# alarmlight_v1_0.net
KiCad netlist of a schematic drawn in Altium Designer
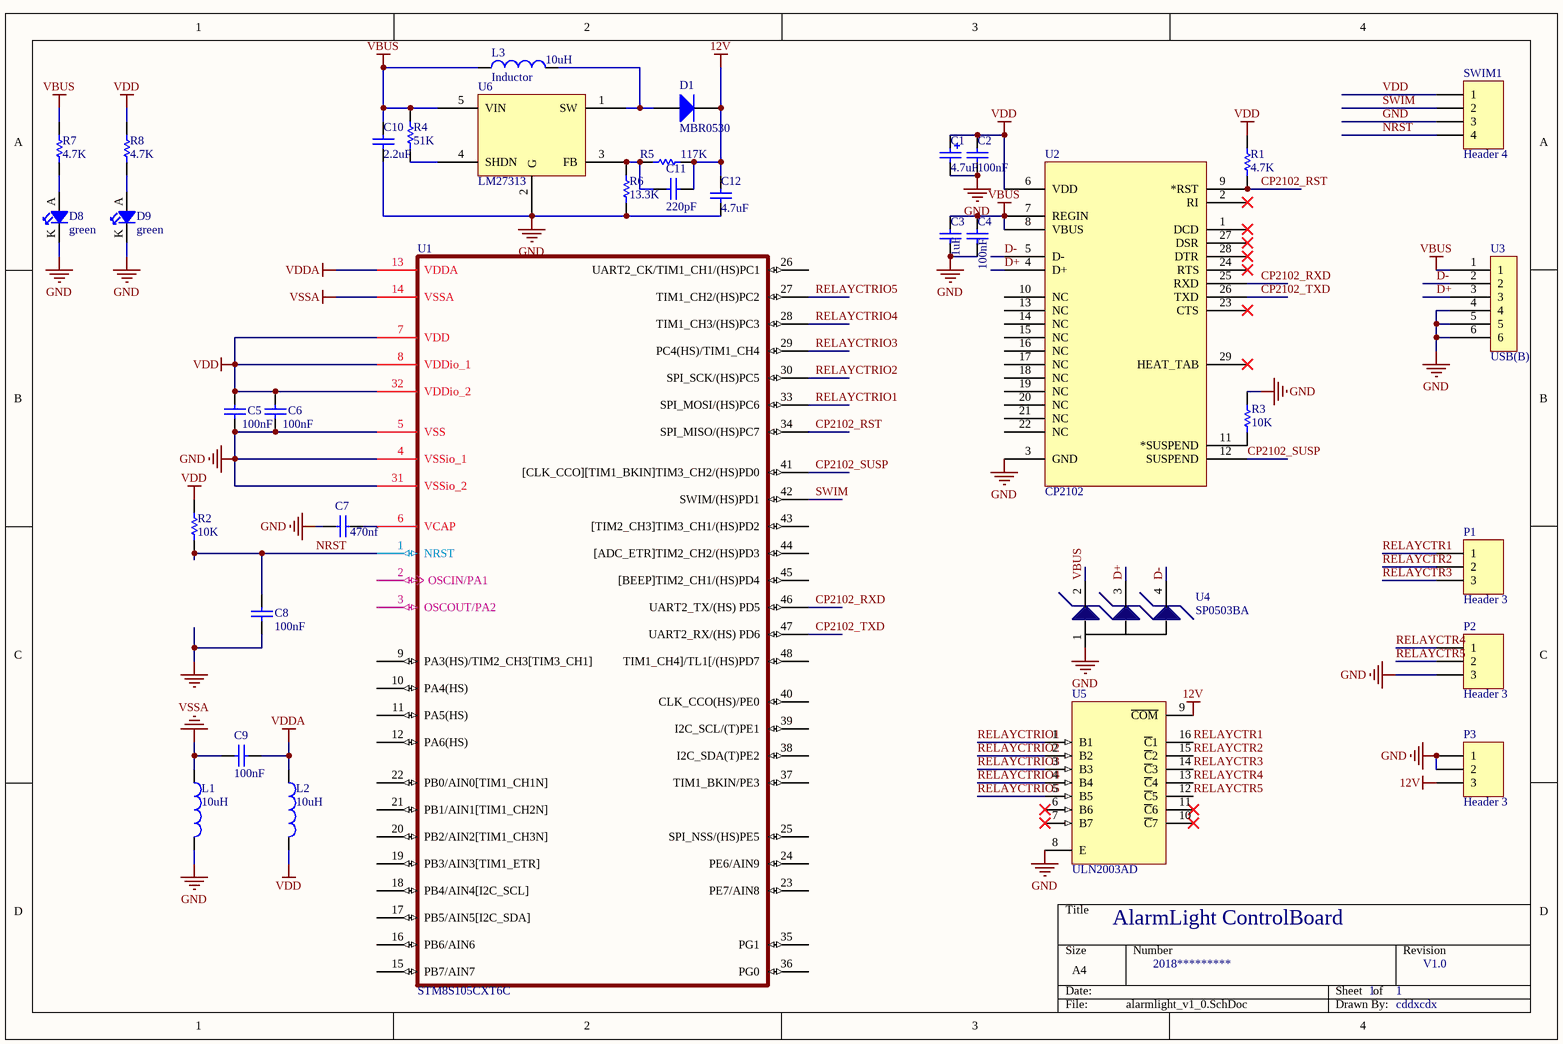
[diagram p0: alarmlight_v1_0.SchDoc]

(export (version "E")
  (design (tool "Eeschema 10.0.6"))
  (components
    (comp (ref "C1")
      (value "4.7uF")
      (footprint "TC3216")
      (description "Polarized Capacitor (Radial)")
      (fields (field (name "PUBLISHER") "Altium Limited"))
      (libsource (lib "MPU_V5") (part "Cap Pol1_4"))
    )
    (comp (ref "C2")
      (value "100nF")
      (footprint "0805C")
      (description "Capacitor")
      (fields (field (name "PUBLISHER") "Altium Limited"))
      (libsource (lib "Miscellaneous Devices") (part "CAP"))
    )
    (comp (ref "C3")
      (value "1uF")
      (footprint "0805C")
      (description "Capacitor")
      (fields (field (name "PUBLISHER") "Altium Limited"))
      (libsource (lib "Miscellaneous Devices") (part "CAP"))
    )
    (comp (ref "C4")
      (value "100nF")
      (footprint "0805C")
      (description "Capacitor")
      (fields (field (name "PUBLISHER") "Altium Limited"))
      (libsource (lib "Miscellaneous Devices") (part "CAP"))
    )
    (comp (ref "C5")
      (value "100nF")
      (footprint "0805C")
      (description "Capacitor")
      (fields (field (name "PUBLISHER") "Altium Limited"))
      (libsource (lib "Miscellaneous Devices") (part "CAP"))
    )
    (comp (ref "C6")
      (value "100nF")
      (footprint "0805C")
      (description "Capacitor")
      (fields (field (name "PUBLISHER") "Altium Limited"))
      (libsource (lib "Miscellaneous Devices") (part "CAP"))
    )
    (comp (ref "C7")
      (value "470nf")
      (footprint "0805C")
      (description "Capacitor")
      (fields (field (name "Comment") "Cap") (field (name "PUBLISHER") "Altium Limited"))
      (libsource (lib "Miscellaneous Devices") (part "Cap"))
    )
    (comp (ref "C8")
      (value "100nF")
      (footprint "0805C")
      (description "Capacitor")
      (fields (field (name "PUBLISHER") "Altium Limited"))
      (libsource (lib "Miscellaneous Devices") (part "CAP"))
    )
    (comp (ref "C9")
      (value "100nF")
      (footprint "0805C")
      (description "Capacitor")
      (fields (field (name "PUBLISHER") "Altium Limited"))
      (libsource (lib "Miscellaneous Devices") (part "CAP"))
    )
    (comp (ref "C10")
      (value "2.2uF")
      (footprint "0805C")
      (description "Capacitor")
      (fields (field (name "PUBLISHER") "Altium Limited"))
      (libsource (lib "Miscellaneous Devices") (part "CAP"))
    )
    (comp (ref "C11")
      (value "220pF")
      (footprint "0805C")
      (description "Capacitor")
      (fields (field (name "PUBLISHER") "Altium Limited"))
      (libsource (lib "Miscellaneous Devices") (part "CAP"))
    )
    (comp (ref "C12")
      (value "4.7uF")
      (footprint "C-6032")
      (description "Capacitor")
      (fields (field (name "PUBLISHER") "Altium Limited"))
      (libsource (lib "Miscellaneous Devices") (part "CAP"))
    )
    (comp (ref "D1")
      (value "MBR0530")
      (footprint "PcbLib1:SOD_123")
      (description "Default Diode")
      (fields (field (name "PUBLISHER") "Altium Limited"))
      (libsource (lib "Miscellaneous Devices") (part "Diode"))
    )
    (comp (ref "D8")
      (value "green")
      (footprint "Diode-LED-0805")
      (fields (field (name "Comment") "LED-3mm"))
      (libsource (lib "my_sch_lib") (part "Diode-LED-1210"))
    )
    (comp (ref "D9")
      (value "green")
      (footprint "Diode-LED-0805")
      (fields (field (name "Comment") "LED-3mm"))
      (libsource (lib "my_sch_lib") (part "Diode-LED-1210"))
    )
    (comp (ref "L1")
      (value "10uH")
      (footprint "0805R")
      (description "Inductor")
      (fields (field (name "PUBLISHER") "Altium Limited"))
      (libsource (lib "Miscellaneous Devices") (part "Inductor"))
    )
    (comp (ref "L2")
      (value "10uH")
      (footprint "0805R")
      (description "Inductor")
      (fields (field (name "PUBLISHER") "Altium Limited"))
      (libsource (lib "Miscellaneous Devices") (part "Inductor"))
    )
    (comp (ref "L3")
      (value "Inductor")
      (footprint "PcbLib1:SWPA3012")
      (fields (field (name "ALTIUM_VALUE") "10uH") (field (name "PUBLISHER") "Altium Limited"))
      (libsource (lib "Miscellaneous Devices") (part "Inductor"))
    )
    (comp (ref "P1")
      (value "Header 3")
      (description "Header, 3-Pin")
      (fields (field (name "PUBLISHER") "Altium Limited"))
      (libsource (lib "alarmlight") (part "Header 3"))
    )
    (comp (ref "P2")
      (value "Header 3")
      (description "Header, 3-Pin")
      (fields (field (name "PUBLISHER") "Altium Limited"))
      (libsource (lib "alarmlight") (part "Header 3"))
    )
    (comp (ref "P3")
      (value "Header 3")
      (description "Header, 3-Pin")
      (fields (field (name "PUBLISHER") "Altium Limited"))
      (libsource (lib "alarmlight") (part "Header 3"))
    )
    (comp (ref "R1")
      (value "4.7K")
      (footprint "0805R")
      (description "Resistor")
      (fields (field (name "PUBLISHER") "Altium Limited"))
      (libsource (lib "Miscellaneous Devices") (part "res1"))
    )
    (comp (ref "R2")
      (value "10K")
      (footprint "0805R")
      (description "Resistor")
      (fields (field (name "PUBLISHER") "Altium Limited"))
      (libsource (lib "Miscellaneous Devices") (part "res1"))
    )
    (comp (ref "R3")
      (value "10K")
      (footprint "0805R")
      (description "Resistor")
      (fields (field (name "PUBLISHER") "Altium Limited"))
      (libsource (lib "Miscellaneous Devices") (part "res1"))
    )
    (comp (ref "R4")
      (value "51K")
      (footprint "0805R")
      (description "Resistor")
      (fields (field (name "PUBLISHER") "Altium Limited"))
      (libsource (lib "Miscellaneous Devices") (part "res1"))
    )
    (comp (ref "R5")
      (value "117K")
      (footprint "0805R")
      (description "Resistor")
      (fields (field (name "PUBLISHER") "Altium Limited"))
      (libsource (lib "Miscellaneous Devices") (part "res1"))
    )
    (comp (ref "R6")
      (value "13.3K")
      (footprint "0805R")
      (description "Resistor")
      (fields (field (name "PUBLISHER") "Altium Limited"))
      (libsource (lib "Miscellaneous Devices") (part "res1"))
    )
    (comp (ref "R7")
      (value "4.7K")
      (footprint "0805R")
      (description "Resistor")
      (fields (field (name "PUBLISHER") "Altium Limited"))
      (libsource (lib "Miscellaneous Devices") (part "res1"))
    )
    (comp (ref "R8")
      (value "4.7K")
      (footprint "0805R")
      (description "Resistor")
      (fields (field (name "PUBLISHER") "Altium Limited"))
      (libsource (lib "Miscellaneous Devices") (part "res1"))
    )
    (comp (ref "SWIM1")
      (value "Header 4")
      (footprint "HDR1X4")
      (description "Header, 4-Pin")
      (fields (field (name "PUBLISHER") "Altium Limited"))
      (libsource (lib "MPU_V5") (part "Header 4"))
    )
    (comp (ref "U1")
      (value "STM8S105CXT6C")
      (footprint "LQFP48")
      (description "ST 8-bit  Microcontroller")
      (libsource (lib "Microcontroller Unit") (part "STM8S105C4T6C"))
    )
    (comp (ref "U2")
      (value "CP2102")
      (footprint "QFN28N5X5-0p5P")
      (description "Imported")
      (libsource (lib "CP2102") (part "CP2102"))
    )
    (comp (ref "U3") (value "USB(B)") (footprint "USB2.5-2H4D") (libsource (lib "Schlib1") (part "USB(B)")))
    (comp (ref "U4") (value "SP0503BA") (footprint "SOT143") (libsource (lib "Schlib1") (part "SP0503BA")))
    (comp (ref "U5")
      (value "ULN2003AD")
      (footprint "D016_N")
      (description "Darlington Transistor Array")
      (fields (field (name "PUBLISHER") "Altium Limited"))
      (libsource (lib "Schlib1") (part "ULN2003AD"))
    )
    (comp (ref "U6") (value "LM27313") (footprint "SOT-23-5") (libsource (lib "Schlib1") (part "LM27313")))
  )
  (nets
    (net (code "1") (name "/CP2102_RST") (class "Default")
      (node (ref "R1") (pin "1") (pinfunction "1_1") (pintype "passive"))
      (node (ref "U1") (pin "34") (pinfunction "SPI_MISO/(HS)PC7_34") (pintype "bidirectional"))
      (node (ref "U2") (pin "9") (pinfunction "*RST_9") (pintype "passive"))
    )
    (net (code "2") (name "/CP2102_RXD") (class "Default")
      (node (ref "U1") (pin "46") (pinfunction "UART2_TX/(HS)_PD5_46") (pintype "bidirectional"))
      (node (ref "U2") (pin "25") (pinfunction "RXD_25") (pintype "passive"))
    )
    (net (code "3") (name "/CP2102_SUSP") (class "Default")
      (node (ref "U1") (pin "41") (pinfunction "[CLK_CCO][TIM1_BKIN]TIM3_CH2/(HS)PD0_41") (pintype "bidirectional"))
      (node (ref "U2") (pin "12") (pinfunction "SUSPEND_12") (pintype "passive"))
    )
    (net (code "4") (name "/CP2102_TXD") (class "Default")
      (node (ref "U1") (pin "47") (pinfunction "UART2_RX/(HS)_PD6_47") (pintype "bidirectional"))
      (node (ref "U2") (pin "26") (pinfunction "TXD_26") (pintype "passive"))
    )
    (net (code "5") (name "/D+") (class "Default")
      (node (ref "U2") (pin "4") (pinfunction "D+_4") (pintype "passive"))
      (node (ref "U3") (pin "3") (pinfunction "3_3") (pintype "passive"))
      (node (ref "U4") (pin "3") (pinfunction "3_3") (pintype "passive"))
    )
    (net (code "6") (name "/D-") (class "Default")
      (node (ref "U2") (pin "5") (pinfunction "D-_5") (pintype "passive"))
      (node (ref "U3") (pin "2") (pinfunction "2_2") (pintype "passive"))
      (node (ref "U4") (pin "4") (pinfunction "4_4") (pintype "passive"))
    )
    (net (code "7") (name "/NRST") (class "Default")
      (node (ref "C8") (pin "2") (pinfunction "2_2") (pintype "passive"))
      (node (ref "R2") (pin "1") (pinfunction "1_1") (pintype "passive"))
      (node (ref "SWIM1") (pin "4") (pinfunction "4_4") (pintype "passive"))
      (node (ref "U1") (pin "1") (pinfunction "NRST_1") (pintype "bidirectional"))
    )
    (net (code "8") (name "/RELAYCTR1") (class "Default")
      (node (ref "P1") (pin "1") (pinfunction "1_1") (pintype "passive"))
      (node (ref "U5") (pin "16") (pinfunction "~{C}1_16") (pintype "open_collector"))
    )
    (net (code "9") (name "/RELAYCTR2") (class "Default")
      (node (ref "P1") (pin "2") (pinfunction "2_2") (pintype "passive"))
      (node (ref "U5") (pin "15") (pinfunction "~{C}2_15") (pintype "open_collector"))
    )
    (net (code "10") (name "/RELAYCTR3") (class "Default")
      (node (ref "P1") (pin "3") (pinfunction "3_3") (pintype "passive"))
      (node (ref "U5") (pin "14") (pinfunction "~{C}3_14") (pintype "open_collector"))
    )
    (net (code "11") (name "/RELAYCTR4") (class "Default")
      (node (ref "P2") (pin "1") (pinfunction "1_1") (pintype "passive"))
      (node (ref "U5") (pin "13") (pinfunction "~{C}4_13") (pintype "open_collector"))
    )
    (net (code "12") (name "/RELAYCTR5") (class "Default")
      (node (ref "P2") (pin "2") (pinfunction "2_2") (pintype "passive"))
      (node (ref "U5") (pin "12") (pinfunction "~{C}5_12") (pintype "open_collector"))
    )
    (net (code "13") (name "/RELAYCTRIO1") (class "Default")
      (node (ref "U1") (pin "33") (pinfunction "SPI_MOSI/(HS)PC6_33") (pintype "bidirectional"))
      (node (ref "U5") (pin "1") (pinfunction "B1_1") (pintype "input"))
    )
    (net (code "14") (name "/RELAYCTRIO2") (class "Default")
      (node (ref "U1") (pin "30") (pinfunction "SPI_SCK/(HS)PC5_30") (pintype "bidirectional"))
      (node (ref "U5") (pin "2") (pinfunction "B2_2") (pintype "input"))
    )
    (net (code "15") (name "/RELAYCTRIO3") (class "Default")
      (node (ref "U1") (pin "29") (pinfunction "PC4(HS)/TIM1_CH4_29") (pintype "bidirectional"))
      (node (ref "U5") (pin "3") (pinfunction "B3_3") (pintype "input"))
    )
    (net (code "16") (name "/RELAYCTRIO4") (class "Default")
      (node (ref "U1") (pin "28") (pinfunction "TIM1_CH3/(HS)PC3_28") (pintype "bidirectional"))
      (node (ref "U5") (pin "4") (pinfunction "B4_4") (pintype "input"))
    )
    (net (code "17") (name "/RELAYCTRIO5") (class "Default")
      (node (ref "U1") (pin "27") (pinfunction "TIM1_CH2/(HS)PC2_27") (pintype "bidirectional"))
      (node (ref "U5") (pin "5") (pinfunction "B5_5") (pintype "input"))
    )
    (net (code "18") (name "/SWIM") (class "Default")
      (node (ref "SWIM1") (pin "2") (pinfunction "2_2") (pintype "passive"))
      (node (ref "U1") (pin "42") (pinfunction "SWIM/(HS)PD1_42") (pintype "bidirectional"))
    )
    (net (code "19") (name "12V") (class "Default")
      (node (ref "C11") (pin "1") (pinfunction "1_1") (pintype "passive"))
      (node (ref "C12") (pin "2") (pinfunction "2_2") (pintype "passive"))
      (node (ref "D1") (pin "2") (pinfunction "K_2") (pintype "passive"))
      (node (ref "P3") (pin "3") (pinfunction "3_3") (pintype "passive"))
      (node (ref "R5") (pin "1") (pinfunction "1_1") (pintype "passive"))
      (node (ref "U5") (pin "9") (pinfunction "~{COM}_9") (pintype "passive"))
    )
    (net (code "20") (name "GND") (class "Default")
      (node (ref "C1") (pin "2") (pinfunction "2_2") (pintype "passive"))
      (node (ref "C10") (pin "1") (pinfunction "1_1") (pintype "passive"))
      (node (ref "C12") (pin "1") (pinfunction "1_1") (pintype "passive"))
      (node (ref "C2") (pin "1") (pinfunction "1_1") (pintype "passive"))
      (node (ref "C3") (pin "1") (pinfunction "1_1") (pintype "passive"))
      (node (ref "C4") (pin "1") (pinfunction "1_1") (pintype "passive"))
      (node (ref "C5") (pin "1") (pinfunction "1_1") (pintype "passive"))
      (node (ref "C6") (pin "1") (pinfunction "1_1") (pintype "passive"))
      (node (ref "C7") (pin "1") (pinfunction "1_1") (pintype "passive"))
      (node (ref "C8") (pin "1") (pinfunction "1_1") (pintype "passive"))
      (node (ref "D8") (pin "K") (pinfunction "K_K") (pintype "passive"))
      (node (ref "D9") (pin "K") (pinfunction "K_K") (pintype "passive"))
      (node (ref "L1") (pin "2") (pinfunction "2_2") (pintype "passive"))
      (node (ref "P2") (pin "3") (pinfunction "3_3") (pintype "passive"))
      (node (ref "P3") (pin "1") (pinfunction "1_1") (pintype "passive"))
      (node (ref "P3") (pin "2") (pinfunction "2_2") (pintype "passive"))
      (node (ref "R3") (pin "1") (pinfunction "1_1") (pintype "passive"))
      (node (ref "R6") (pin "1") (pinfunction "1_1") (pintype "passive"))
      (node (ref "SWIM1") (pin "3") (pinfunction "3_3") (pintype "passive"))
      (node (ref "U1") (pin "31") (pinfunction "VSSio_2_31") (pintype "power_in"))
      (node (ref "U1") (pin "4") (pinfunction "VSSio_1_4") (pintype "power_in"))
      (node (ref "U1") (pin "5") (pinfunction "VSS_5") (pintype "power_in"))
      (node (ref "U2") (pin "3") (pinfunction "GND_3") (pintype "passive"))
      (node (ref "U3") (pin "4") (pinfunction "4_4") (pintype "passive"))
      (node (ref "U3") (pin "5") (pinfunction "5_5") (pintype "passive"))
      (node (ref "U3") (pin "6") (pinfunction "6_6") (pintype "passive"))
      (node (ref "U4") (pin "1") (pinfunction "1_1") (pintype "passive"))
      (node (ref "U5") (pin "8") (pinfunction "E_8") (pintype "power_in"))
      (node (ref "U6") (pin "2") (pinfunction "G_2") (pintype "passive"))
    )
    (net (code "21") (name "Net-(D1-A)") (class "Default")
      (node (ref "D1") (pin "1") (pinfunction "A_1") (pintype "passive"))
      (node (ref "L3") (pin "2") (pinfunction "2_2") (pintype "passive"))
      (node (ref "U6") (pin "1") (pinfunction "SW_1") (pintype "passive"))
    )
    (net (code "22") (name "Net-(D8-PadA)") (class "Default")
      (node (ref "D8") (pin "A") (pinfunction "A_A") (pintype "passive"))
      (node (ref "R7") (pin "1") (pinfunction "1_1") (pintype "passive"))
    )
    (net (code "23") (name "Net-(D9-PadA)") (class "Default")
      (node (ref "D9") (pin "A") (pinfunction "A_A") (pintype "passive"))
      (node (ref "R8") (pin "1") (pinfunction "1_1") (pintype "passive"))
    )
    (net (code "24") (name "Net-(U1-VCAP)") (class "Default")
      (node (ref "C7") (pin "2") (pinfunction "2_2") (pintype "passive"))
      (node (ref "U1") (pin "6") (pinfunction "VCAP_6") (pintype "power_in"))
    )
    (net (code "25") (name "Net-(U2-*SUSPEND)") (class "Default")
      (node (ref "R3") (pin "2") (pinfunction "2_2") (pintype "passive"))
      (node (ref "U2") (pin "11") (pinfunction "*SUSPEND_11") (pintype "passive"))
    )
    (net (code "26") (name "Net-(U6-FB)") (class "Default")
      (node (ref "C11") (pin "2") (pinfunction "2_2") (pintype "passive"))
      (node (ref "R5") (pin "2") (pinfunction "2_2") (pintype "passive"))
      (node (ref "R6") (pin "2") (pinfunction "2_2") (pintype "passive"))
      (node (ref "U6") (pin "3") (pinfunction "FB_3") (pintype "passive"))
    )
    (net (code "27") (name "Net-(U6-SHDN)") (class "Default")
      (node (ref "R4") (pin "1") (pinfunction "1_1") (pintype "passive"))
      (node (ref "U6") (pin "4") (pinfunction "SHDN_4") (pintype "passive"))
    )
    (net (code "28") (name "VBUS") (class "Default")
      (node (ref "C10") (pin "2") (pinfunction "2_2") (pintype "passive"))
      (node (ref "C3") (pin "2") (pinfunction "2_2") (pintype "passive"))
      (node (ref "C4") (pin "2") (pinfunction "2_2") (pintype "passive"))
      (node (ref "L3") (pin "1") (pinfunction "1_1") (pintype "passive"))
      (node (ref "R4") (pin "2") (pinfunction "2_2") (pintype "passive"))
      (node (ref "R7") (pin "2") (pinfunction "2_2") (pintype "passive"))
      (node (ref "U2") (pin "7") (pinfunction "REGIN_7") (pintype "passive"))
      (node (ref "U2") (pin "8") (pinfunction "VBUS_8") (pintype "passive"))
      (node (ref "U3") (pin "1") (pinfunction "1_1") (pintype "passive"))
      (node (ref "U4") (pin "2") (pinfunction "2_2") (pintype "passive"))
      (node (ref "U6") (pin "5") (pinfunction "VIN_5") (pintype "passive"))
    )
    (net (code "29") (name "VDD") (class "Default")
      (node (ref "C1") (pin "1") (pinfunction "1_1") (pintype "passive"))
      (node (ref "C2") (pin "2") (pinfunction "2_2") (pintype "passive"))
      (node (ref "C5") (pin "2") (pinfunction "2_2") (pintype "passive"))
      (node (ref "C6") (pin "2") (pinfunction "2_2") (pintype "passive"))
      (node (ref "L2") (pin "2") (pinfunction "2_2") (pintype "passive"))
      (node (ref "R1") (pin "2") (pinfunction "2_2") (pintype "passive"))
      (node (ref "R2") (pin "2") (pinfunction "2_2") (pintype "passive"))
      (node (ref "R8") (pin "2") (pinfunction "2_2") (pintype "passive"))
      (node (ref "SWIM1") (pin "1") (pinfunction "1_1") (pintype "passive"))
      (node (ref "U1") (pin "32") (pinfunction "VDDio_2_32") (pintype "power_in"))
      (node (ref "U1") (pin "7") (pinfunction "VDD_7") (pintype "power_in"))
      (node (ref "U1") (pin "8") (pinfunction "VDDio_1_8") (pintype "power_in"))
      (node (ref "U2") (pin "6") (pinfunction "VDD_6") (pintype "passive"))
    )
    (net (code "30") (name "VDDA") (class "Default")
      (node (ref "C9") (pin "2") (pinfunction "2_2") (pintype "passive"))
      (node (ref "L2") (pin "1") (pinfunction "1_1") (pintype "passive"))
      (node (ref "U1") (pin "13") (pinfunction "VDDA_13") (pintype "power_in"))
    )
    (net (code "31") (name "VSSA") (class "Default")
      (node (ref "C9") (pin "1") (pinfunction "1_1") (pintype "passive"))
      (node (ref "L1") (pin "1") (pinfunction "1_1") (pintype "passive"))
      (node (ref "U1") (pin "14") (pinfunction "VSSA_14") (pintype "power_in"))
    )
    (net (code "32") (name "unconnected-(U1-CLK_CCO(HS){slash}PE0-Pad40)") (class "Default")
      (node (ref "U1") (pin "40") (pinfunction "CLK_CCO(HS)/PE0_40") (pintype "bidirectional"))
    )
    (net (code "33") (name "unconnected-(U1-I2C_SCL{slash}(T)PE1-Pad39)") (class "Default")
      (node (ref "U1") (pin "39") (pinfunction "I2C_SCL/(T)PE1_39") (pintype "bidirectional"))
    )
    (net (code "34") (name "unconnected-(U1-I2C_SDA(T)PE2-Pad38)") (class "Default")
      (node (ref "U1") (pin "38") (pinfunction "I2C_SDA(T)PE2_38") (pintype "bidirectional"))
    )
    (net (code "35") (name "unconnected-(U1-OSCIN{slash}PA1-Pad2)") (class "Default")
      (node (ref "U1") (pin "2") (pinfunction "OSCIN/PA1_2") (pintype "bidirectional"))
    )
    (net (code "36") (name "unconnected-(U1-OSCOUT{slash}PA2-Pad3)") (class "Default")
      (node (ref "U1") (pin "3") (pinfunction "OSCOUT/PA2_3") (pintype "bidirectional"))
    )
    (net (code "37") (name "unconnected-(U1-PA3(HS){slash}TIM2_CH3[TIM3_CH1]-Pad9)") (class "Default")
      (node (ref "U1") (pin "9") (pinfunction "PA3(HS)/TIM2_CH3[TIM3_CH1]_9") (pintype "bidirectional"))
    )
    (net (code "38") (name "unconnected-(U1-PA4(HS)-Pad10)") (class "Default")
      (node (ref "U1") (pin "10") (pinfunction "PA4(HS)_10") (pintype "bidirectional"))
    )
    (net (code "39") (name "unconnected-(U1-PA5(HS)-Pad11)") (class "Default")
      (node (ref "U1") (pin "11") (pinfunction "PA5(HS)_11") (pintype "bidirectional"))
    )
    (net (code "40") (name "unconnected-(U1-PA6(HS)-Pad12)") (class "Default")
      (node (ref "U1") (pin "12") (pinfunction "PA6(HS)_12") (pintype "bidirectional"))
    )
    (net (code "41") (name "unconnected-(U1-PB0{slash}AIN0[TIM1_CH1N]-Pad22)") (class "Default")
      (node (ref "U1") (pin "22") (pinfunction "PB0/AIN0[TIM1_CH1N]_22") (pintype "bidirectional"))
    )
    (net (code "42") (name "unconnected-(U1-PB1{slash}AIN1[TIM1_CH2N]-Pad21)") (class "Default")
      (node (ref "U1") (pin "21") (pinfunction "PB1/AIN1[TIM1_CH2N]_21") (pintype "bidirectional"))
    )
    (net (code "43") (name "unconnected-(U1-PB2{slash}AIN2[TIM1_CH3N]-Pad20)") (class "Default")
      (node (ref "U1") (pin "20") (pinfunction "PB2/AIN2[TIM1_CH3N]_20") (pintype "bidirectional"))
    )
    (net (code "44") (name "unconnected-(U1-PB3{slash}AIN3[TIM1_ETR]-Pad19)") (class "Default")
      (node (ref "U1") (pin "19") (pinfunction "PB3/AIN3[TIM1_ETR]_19") (pintype "bidirectional"))
    )
    (net (code "45") (name "unconnected-(U1-PB4{slash}AIN4[I2C_SCL]-Pad18)") (class "Default")
      (node (ref "U1") (pin "18") (pinfunction "PB4/AIN4[I2C_SCL]_18") (pintype "bidirectional"))
    )
    (net (code "46") (name "unconnected-(U1-PB5{slash}AIN5[I2C_SDA]-Pad17)") (class "Default")
      (node (ref "U1") (pin "17") (pinfunction "PB5/AIN5[I2C_SDA]_17") (pintype "bidirectional"))
    )
    (net (code "47") (name "unconnected-(U1-PB6{slash}AIN6-Pad16)") (class "Default")
      (node (ref "U1") (pin "16") (pinfunction "PB6/AIN6_16") (pintype "bidirectional"))
    )
    (net (code "48") (name "unconnected-(U1-PB7{slash}AIN7-Pad15)") (class "Default")
      (node (ref "U1") (pin "15") (pinfunction "PB7/AIN7_15") (pintype "bidirectional"))
    )
    (net (code "49") (name "unconnected-(U1-PE6{slash}AIN9-Pad24)") (class "Default")
      (node (ref "U1") (pin "24") (pinfunction "PE6/AIN9_24") (pintype "bidirectional"))
    )
    (net (code "50") (name "unconnected-(U1-PE7{slash}AIN8-Pad23)") (class "Default")
      (node (ref "U1") (pin "23") (pinfunction "PE7/AIN8_23") (pintype "bidirectional"))
    )
    (net (code "51") (name "unconnected-(U1-PG0-Pad36)") (class "Default")
      (node (ref "U1") (pin "36") (pinfunction "PG0_36") (pintype "bidirectional"))
    )
    (net (code "52") (name "unconnected-(U1-PG1-Pad35)") (class "Default")
      (node (ref "U1") (pin "35") (pinfunction "PG1_35") (pintype "bidirectional"))
    )
    (net (code "53") (name "unconnected-(U1-SPI_NSS{slash}(HS)PE5-Pad25)") (class "Default")
      (node (ref "U1") (pin "25") (pinfunction "SPI_NSS/(HS)PE5_25") (pintype "bidirectional"))
    )
    (net (code "54") (name "unconnected-(U1-TIM1_BKIN{slash}PE3-Pad37)") (class "Default")
      (node (ref "U1") (pin "37") (pinfunction "TIM1_BKIN/PE3_37") (pintype "bidirectional"))
    )
    (net (code "55") (name "unconnected-(U1-TIM1_CH4]{slash}TL1[{slash}(HS)PD7-Pad48)") (class "Default")
      (node (ref "U1") (pin "48") (pinfunction "TIM1_CH4]/TL1[/(HS)PD7_48") (pintype "bidirectional"))
    )
    (net (code "56") (name "unconnected-(U1-UART2_CK{slash}TIM1_CH1{slash}(HS)PC1-Pad26)") (class "Default")
      (node (ref "U1") (pin "26") (pinfunction "UART2_CK/TIM1_CH1/(HS)PC1_26") (pintype "bidirectional"))
    )
    (net (code "57") (name "unconnected-(U1-[ADC_ETR]TIM2_CH2{slash}(HS)PD3-Pad44)") (class "Default")
      (node (ref "U1") (pin "44") (pinfunction "[ADC_ETR]TIM2_CH2/(HS)PD3_44") (pintype "bidirectional"))
    )
    (net (code "58") (name "unconnected-(U1-[BEEP]TIM2_CH1{slash}(HS)PD4-Pad45)") (class "Default")
      (node (ref "U1") (pin "45") (pinfunction "[BEEP]TIM2_CH1/(HS)PD4_45") (pintype "bidirectional"))
    )
    (net (code "59") (name "unconnected-(U1-[TIM2_CH3]TIM3_CH1{slash}(HS)PD2-Pad43)") (class "Default")
      (node (ref "U1") (pin "43") (pinfunction "[TIM2_CH3]TIM3_CH1/(HS)PD2_43") (pintype "bidirectional"))
    )
    (net (code "60") (name "unconnected-(U2-CTS-Pad23)") (class "Default")
      (node (ref "U2") (pin "23") (pinfunction "CTS_23") (pintype "passive+no_connect"))
    )
    (net (code "61") (name "unconnected-(U2-DCD-Pad1)") (class "Default")
      (node (ref "U2") (pin "1") (pinfunction "DCD_1") (pintype "passive+no_connect"))
    )
    (net (code "62") (name "unconnected-(U2-DSR-Pad27)") (class "Default")
      (node (ref "U2") (pin "27") (pinfunction "DSR_27") (pintype "passive+no_connect"))
    )
    (net (code "63") (name "unconnected-(U2-DTR-Pad28)") (class "Default")
      (node (ref "U2") (pin "28") (pinfunction "DTR_28") (pintype "passive+no_connect"))
    )
    (net (code "64") (name "unconnected-(U2-HEAT_TAB-Pad29)") (class "Default")
      (node (ref "U2") (pin "29") (pinfunction "HEAT_TAB_29") (pintype "passive+no_connect"))
    )
    (net (code "65") (name "unconnected-(U2-NC-Pad10)") (class "Default")
      (node (ref "U2") (pin "10") (pinfunction "NC_10") (pintype "passive"))
    )
    (net (code "66") (name "unconnected-(U2-NC-Pad13)") (class "Default")
      (node (ref "U2") (pin "13") (pinfunction "NC_13") (pintype "passive"))
    )
    (net (code "67") (name "unconnected-(U2-NC-Pad14)") (class "Default")
      (node (ref "U2") (pin "14") (pinfunction "NC_14") (pintype "passive"))
    )
    (net (code "68") (name "unconnected-(U2-NC-Pad15)") (class "Default")
      (node (ref "U2") (pin "15") (pinfunction "NC_15") (pintype "passive"))
    )
    (net (code "69") (name "unconnected-(U2-NC-Pad16)") (class "Default")
      (node (ref "U2") (pin "16") (pinfunction "NC_16") (pintype "passive"))
    )
    (net (code "70") (name "unconnected-(U2-NC-Pad17)") (class "Default")
      (node (ref "U2") (pin "17") (pinfunction "NC_17") (pintype "passive"))
    )
    (net (code "71") (name "unconnected-(U2-NC-Pad18)") (class "Default")
      (node (ref "U2") (pin "18") (pinfunction "NC_18") (pintype "passive"))
    )
    (net (code "72") (name "unconnected-(U2-NC-Pad19)") (class "Default")
      (node (ref "U2") (pin "19") (pinfunction "NC_19") (pintype "passive"))
    )
    (net (code "73") (name "unconnected-(U2-NC-Pad20)") (class "Default")
      (node (ref "U2") (pin "20") (pinfunction "NC_20") (pintype "passive"))
    )
    (net (code "74") (name "unconnected-(U2-NC-Pad21)") (class "Default")
      (node (ref "U2") (pin "21") (pinfunction "NC_21") (pintype "passive"))
    )
    (net (code "75") (name "unconnected-(U2-NC-Pad22)") (class "Default")
      (node (ref "U2") (pin "22") (pinfunction "NC_22") (pintype "passive"))
    )
    (net (code "76") (name "unconnected-(U2-RI-Pad2)") (class "Default")
      (node (ref "U2") (pin "2") (pinfunction "RI_2") (pintype "passive+no_connect"))
    )
    (net (code "77") (name "unconnected-(U2-RTS-Pad24)") (class "Default")
      (node (ref "U2") (pin "24") (pinfunction "RTS_24") (pintype "passive+no_connect"))
    )
    (net (code "78") (name "unconnected-(U5-B6-Pad6)") (class "Default")
      (node (ref "U5") (pin "6") (pinfunction "B6_6") (pintype "input+no_connect"))
    )
    (net (code "79") (name "unconnected-(U5-B7-Pad7)") (class "Default")
      (node (ref "U5") (pin "7") (pinfunction "B7_7") (pintype "input+no_connect"))
    )
    (net (code "80") (name "unconnected-(U5-~{C}6-Pad11)") (class "Default")
      (node (ref "U5") (pin "11") (pinfunction "~{C}6_11") (pintype "open_collector+no_connect"))
    )
    (net (code "81") (name "unconnected-(U5-~{C}7-Pad10)") (class "Default")
      (node (ref "U5") (pin "10") (pinfunction "~{C}7_10") (pintype "open_collector+no_connect"))
    )
  )
)
